# Sheet1.net
KiCad netlist of a schematic drawn in Altium Designer
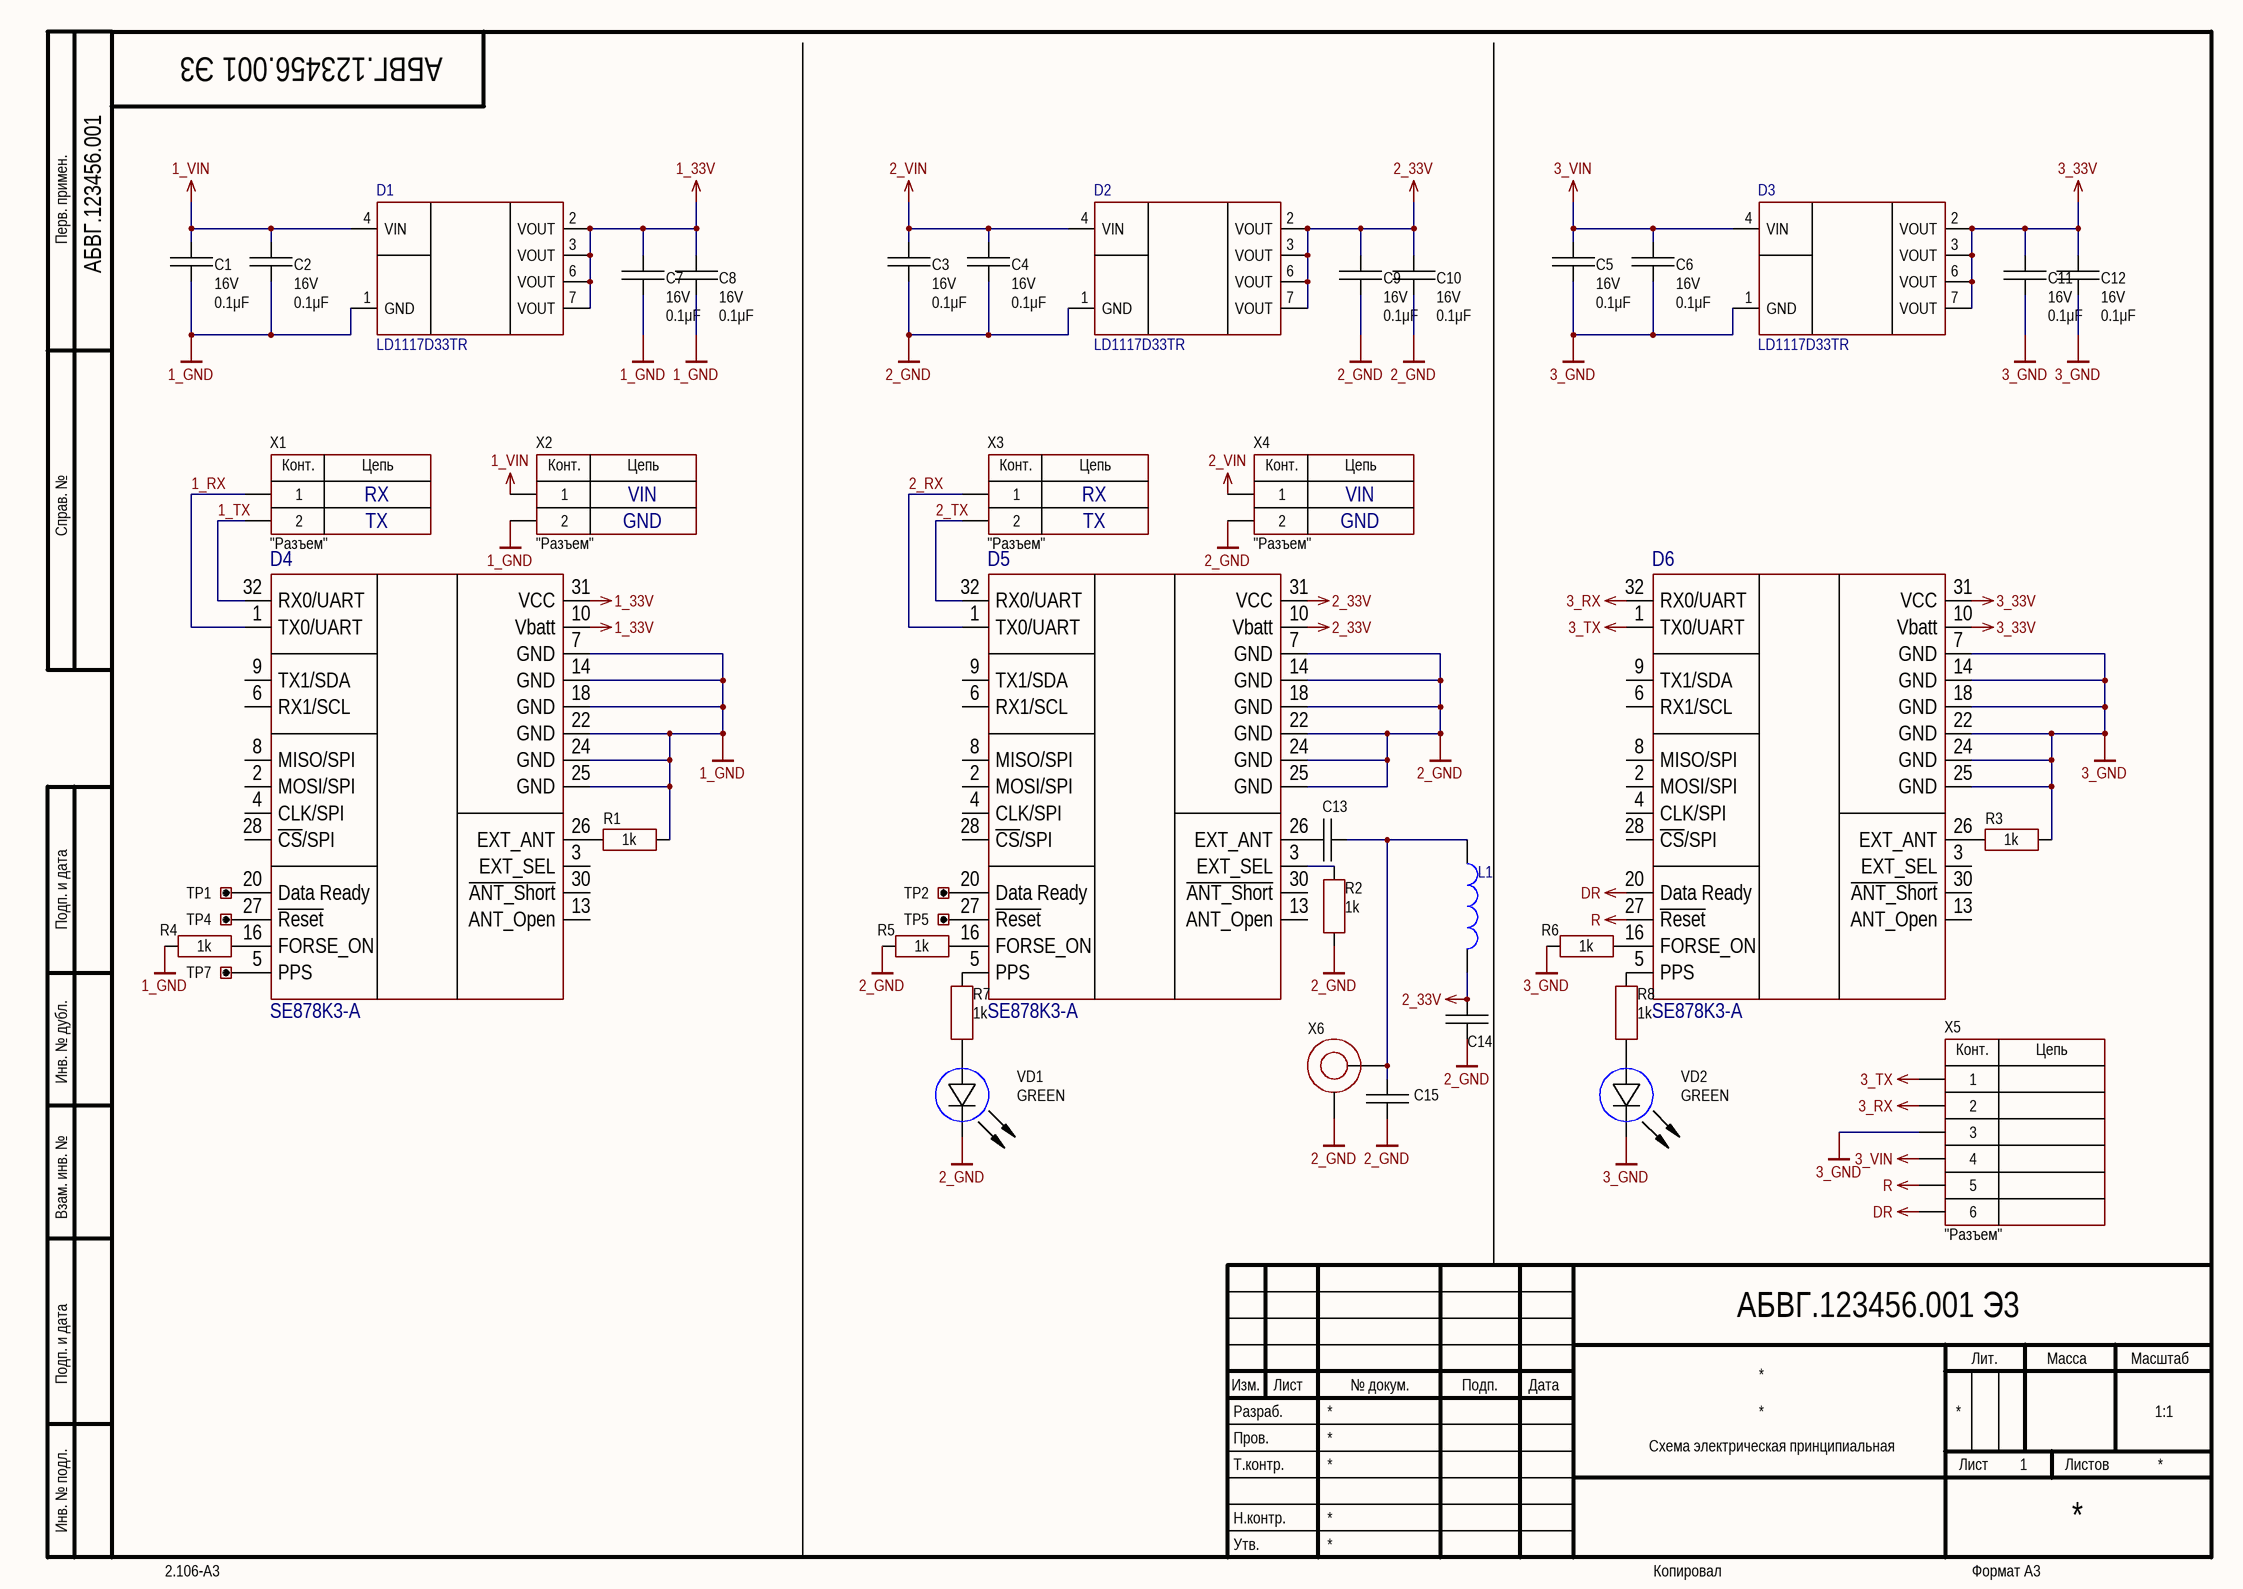
[diagram p0: Sheet1.SchDoc]

(export (version "E")
  (design (tool "Eeschema 10.0.6"))
  (components
    (comp (ref "C1")
      (value "0.1μF")
      (footprint "CAP: 0603")
      (fields
        (field (name "MANUFACTURER") "Yageo")
        (field (name "PARTNUMBER") "CC0603KRX7R7BB104")
        (field (name "VALUEMANUFACTURERPARTNUMBER") "Ceramic capacitor, 0.1μF, X7R, ±10%, 16V, 0603, -55...+125°C")
        (field (name "VOLTAGE") "16V")
      )
      (libsource (lib "Capacitor") (part "Ceramic_0603"))
    )
    (comp (ref "C2")
      (value "0.1μF")
      (footprint "CAP: 0603")
      (fields
        (field (name "MANUFACTURER") "Yageo")
        (field (name "PARTNUMBER") "CC0603KRX7R7BB104")
        (field (name "VALUEMANUFACTURERPARTNUMBER") "Ceramic capacitor, 0.1μF, X7R, ±10%, 16V, 0603, -55...+125°C")
        (field (name "VOLTAGE") "16V")
      )
      (libsource (lib "Capacitor") (part "Ceramic_0603"))
    )
    (comp (ref "C3")
      (value "0.1μF")
      (footprint "CAP: 0603")
      (fields
        (field (name "MANUFACTURER") "Yageo")
        (field (name "PARTNUMBER") "CC0603KRX7R7BB104")
        (field (name "VALUEMANUFACTURERPARTNUMBER") "Ceramic capacitor, 0.1μF, X7R, ±10%, 16V, 0603, -55...+125°C")
        (field (name "VOLTAGE") "16V")
      )
      (libsource (lib "Capacitor") (part "Ceramic_0603"))
    )
    (comp (ref "C4")
      (value "0.1μF")
      (footprint "CAP: 0603")
      (fields
        (field (name "MANUFACTURER") "Yageo")
        (field (name "PARTNUMBER") "CC0603KRX7R7BB104")
        (field (name "VALUEMANUFACTURERPARTNUMBER") "Ceramic capacitor, 0.1μF, X7R, ±10%, 16V, 0603, -55...+125°C")
        (field (name "VOLTAGE") "16V")
      )
      (libsource (lib "Capacitor") (part "Ceramic_0603"))
    )
    (comp (ref "C5")
      (value "0.1μF")
      (footprint "CAP: 0603")
      (fields
        (field (name "MANUFACTURER") "Yageo")
        (field (name "PARTNUMBER") "CC0603KRX7R7BB104")
        (field (name "VALUEMANUFACTURERPARTNUMBER") "Ceramic capacitor, 0.1μF, X7R, ±10%, 16V, 0603, -55...+125°C")
        (field (name "VOLTAGE") "16V")
      )
      (libsource (lib "Capacitor") (part "Ceramic_0603"))
    )
    (comp (ref "C6")
      (value "0.1μF")
      (footprint "CAP: 0603")
      (fields
        (field (name "MANUFACTURER") "Yageo")
        (field (name "PARTNUMBER") "CC0603KRX7R7BB104")
        (field (name "VALUEMANUFACTURERPARTNUMBER") "Ceramic capacitor, 0.1μF, X7R, ±10%, 16V, 0603, -55...+125°C")
        (field (name "VOLTAGE") "16V")
      )
      (libsource (lib "Capacitor") (part "Ceramic_0603"))
    )
    (comp (ref "C7")
      (value "0.1μF")
      (footprint "CAP: 0603")
      (fields
        (field (name "MANUFACTURER") "Yageo")
        (field (name "PARTNUMBER") "CC0603KRX7R7BB104")
        (field (name "VALUEMANUFACTURERPARTNUMBER") "Ceramic capacitor, 0.1μF, X7R, ±10%, 16V, 0603, -55...+125°C")
        (field (name "VOLTAGE") "16V")
      )
      (libsource (lib "Capacitor") (part "Ceramic_0603"))
    )
    (comp (ref "C8")
      (value "0.1μF")
      (footprint "CAP: 0603")
      (fields
        (field (name "MANUFACTURER") "Yageo")
        (field (name "PARTNUMBER") "CC0603KRX7R7BB104")
        (field (name "VALUEMANUFACTURERPARTNUMBER") "Ceramic capacitor, 0.1μF, X7R, ±10%, 16V, 0603, -55...+125°C")
        (field (name "VOLTAGE") "16V")
      )
      (libsource (lib "Capacitor") (part "Ceramic_0603"))
    )
    (comp (ref "C9")
      (value "0.1μF")
      (footprint "CAP: 0603")
      (fields
        (field (name "MANUFACTURER") "Yageo")
        (field (name "PARTNUMBER") "CC0603KRX7R7BB104")
        (field (name "VALUEMANUFACTURERPARTNUMBER") "Ceramic capacitor, 0.1μF, X7R, ±10%, 16V, 0603, -55...+125°C")
        (field (name "VOLTAGE") "16V")
      )
      (libsource (lib "Capacitor") (part "Ceramic_0603"))
    )
    (comp (ref "C10")
      (value "0.1μF")
      (footprint "CAP: 0603")
      (fields
        (field (name "MANUFACTURER") "Yageo")
        (field (name "PARTNUMBER") "CC0603KRX7R7BB104")
        (field (name "VALUEMANUFACTURERPARTNUMBER") "Ceramic capacitor, 0.1μF, X7R, ±10%, 16V, 0603, -55...+125°C")
        (field (name "VOLTAGE") "16V")
      )
      (libsource (lib "Capacitor") (part "Ceramic_0603"))
    )
    (comp (ref "C11")
      (value "0.1μF")
      (footprint "CAP: 0603")
      (fields
        (field (name "MANUFACTURER") "Yageo")
        (field (name "PARTNUMBER") "CC0603KRX7R7BB104")
        (field (name "VALUEMANUFACTURERPARTNUMBER") "Ceramic capacitor, 0.1μF, X7R, ±10%, 16V, 0603, -55...+125°C")
        (field (name "VOLTAGE") "16V")
      )
      (libsource (lib "Capacitor") (part "Ceramic_0603"))
    )
    (comp (ref "C12")
      (value "0.1μF")
      (footprint "CAP: 0603")
      (fields
        (field (name "MANUFACTURER") "Yageo")
        (field (name "PARTNUMBER") "CC0603KRX7R7BB104")
        (field (name "VALUEMANUFACTURERPARTNUMBER") "Ceramic capacitor, 0.1μF, X7R, ±10%, 16V, 0603, -55...+125°C")
        (field (name "VOLTAGE") "16V")
      )
      (libsource (lib "Capacitor") (part "Ceramic_0603"))
    )
    (comp (ref "C13")
      (value "~")
      (footprint "CAP: 0603")
      (fields
        (field (name "MANUFACTURER") "Yageo")
        (field (name "PARTNUMBER") "CC0603KRX7R7BB104")
        (field (name "VALUEMANUFACTURERPARTNUMBER") "Ceramic capacitor, 100Пф, NP0, ±10%, 16V, 0603, -55...+125°C")
      )
      (libsource (lib "Capacitor") (part "Ceramic_0603"))
    )
    (comp (ref "C14")
      (value "~")
      (footprint "CAP: 0603")
      (fields
        (field (name "MANUFACTURER") "Yageo")
        (field (name "PARTNUMBER") "CC0603KRX7R7BB104")
        (field (name "VALUEMANUFACTURERPARTNUMBER") "Ceramic capacitor, 100 пФ, NP0, ±10%, 16V, 0603, -55...+125°C")
      )
      (libsource (lib "Capacitor") (part "Ceramic_0603"))
    )
    (comp (ref "C15")
      (value "~")
      (footprint "CAP: 0603")
      (fields
        (field (name "MANUFACTURER") "Yageo")
        (field (name "PARTNUMBER") "CC0603KRX7R7BB104")
        (field (name "VALUEMANUFACTURERPARTNUMBER") "Ceramic capacitor, 2.2 пФ, NP0, ±10%, 16V, 0603, -55...+125°C")
      )
      (libsource (lib "Capacitor") (part "Ceramic_0603"))
    )
    (comp (ref "D1")
      (value "LD1117D33TR")
      (footprint "8-SOIC")
      (description "Linear voltage regulator")
      (fields (field (name "MANUFACTURER") "ST MICROELECTRONICS"))
      (libsource (lib "IC. Power supply") (part "LD1117D33TR"))
    )
    (comp (ref "D2")
      (value "LD1117D33TR")
      (footprint "8-SOIC")
      (description "Linear voltage regulator")
      (fields (field (name "MANUFACTURER") "ST MICROELECTRONICS"))
      (libsource (lib "IC. Power supply") (part "LD1117D33TR"))
    )
    (comp (ref "D3")
      (value "LD1117D33TR")
      (footprint "8-SOIC")
      (description "Linear voltage regulator")
      (fields (field (name "MANUFACTURER") "ST MICROELECTRONICS"))
      (libsource (lib "IC. Power supply") (part "LD1117D33TR"))
    )
    (comp (ref "D4")
      (value "SE878K3-A")
      (footprint "CustomCase:MOD: SE878K3-A")
      (description "Smart Antenna GNSS Receiver Module")
      (fields
        (field (name "MANUFACTURER") "TELIT")
        (field (name "VALUEMANUFACTURERPARTNUMBER") "SE878K3-A TELIT")
      )
      (libsource (lib "Module") (part "SE878K3-A"))
    )
    (comp (ref "D5")
      (value "SE878K3-A")
      (footprint "CustomCase:MOD: SE878K3-A")
      (description "Smart Antenna GNSS Receiver Module")
      (fields
        (field (name "MANUFACTURER") "TELIT")
        (field (name "VALUEMANUFACTURERPARTNUMBER") "SE878K3-A TELIT")
      )
      (libsource (lib "Module") (part "SE878K3-A"))
    )
    (comp (ref "D6")
      (value "SE878K3-A")
      (footprint "CustomCase:MOD: SE878K3-A")
      (description "Smart Antenna GNSS Receiver Module")
      (fields
        (field (name "MANUFACTURER") "TELIT")
        (field (name "VALUEMANUFACTURERPARTNUMBER") "SE878K3-A TELIT")
      )
      (libsource (lib "Module") (part "SE878K3-A"))
    )
    (comp (ref "L1")
      (value "B09TJL")
      (footprint "IND: BxxT")
      (description "Mini Air Core Inductor")
      (fields (field (name "MANUFACTURER") "COILCRAFT") (field (name "TOLERANCE") "+-5%"))
      (libsource (lib "Inductor") (part "Inductor_air"))
    )
    (comp (ref "R1")
      (value "1k")
      (footprint "RES: 0603")
      (fields
        (field (name "MANUFACTURER") "Yageo")
        (field (name "PARTNUMBER") "RC0603JR-07100RL")
        (field (name "VALUEMANUFACTURERPARTNUMBER") "Resistor film, 1k, ±5%, 0603, 0.1W, -55...+125°C")
      )
      (libsource (lib "Resistor") (part "Resistor_0603"))
    )
    (comp (ref "R2")
      (value "1k")
      (footprint "RES: 0603")
      (fields
        (field (name "MANUFACTURER") "Yageo")
        (field (name "PARTNUMBER") "RC0603JR-07100RL")
        (field (name "VALUEMANUFACTURERPARTNUMBER") "Resistor film, 1k, ±5%, 0603, 0.1W, -55...+125°C")
      )
      (libsource (lib "") (part "Resistor_0603_1"))
    )
    (comp (ref "R3")
      (value "1k")
      (footprint "RES: 0603")
      (fields
        (field (name "MANUFACTURER") "Yageo")
        (field (name "PARTNUMBER") "RC0603JR-07100RL")
        (field (name "VALUEMANUFACTURERPARTNUMBER") "Resistor film, 1k, ±5%, 0603, 0.1W, -55...+125°C")
      )
      (libsource (lib "Resistor") (part "Resistor_0603"))
    )
    (comp (ref "R4")
      (value "1k")
      (footprint "RES: 0603")
      (fields
        (field (name "MANUFACTURER") "Yageo")
        (field (name "PARTNUMBER") "RC0603JR-07100RL")
        (field (name "VALUEMANUFACTURERPARTNUMBER") "Resistor film, 1k, ±5%, 0603, 0.1W, -55...+125°C")
      )
      (libsource (lib "Resistor") (part "Resistor_0603"))
    )
    (comp (ref "R5")
      (value "1k")
      (footprint "RES: 0603")
      (fields
        (field (name "MANUFACTURER") "Yageo")
        (field (name "PARTNUMBER") "RC0603JR-07100RL")
        (field (name "VALUEMANUFACTURERPARTNUMBER") "Resistor film, 1k, ±5%, 0603, 0.1W, -55...+125°C")
      )
      (libsource (lib "Resistor") (part "Resistor_0603"))
    )
    (comp (ref "R6")
      (value "1k")
      (footprint "RES: 0603")
      (fields
        (field (name "MANUFACTURER") "Yageo")
        (field (name "PARTNUMBER") "RC0603JR-07100RL")
        (field (name "VALUEMANUFACTURERPARTNUMBER") "Resistor film, 1k, ±5%, 0603, 0.1W, -55...+125°C")
      )
      (libsource (lib "Resistor") (part "Resistor_0603"))
    )
    (comp (ref "R7")
      (value "1k")
      (footprint "RES: 0603")
      (fields
        (field (name "MANUFACTURER") "Yageo")
        (field (name "PARTNUMBER") "RC0603JR-07100RL")
        (field (name "VALUEMANUFACTURERPARTNUMBER") "Resistor film, 1k, ±5%, 0603, 0.1W, -55...+125°C")
      )
      (libsource (lib "") (part "Resistor_0603_1"))
    )
    (comp (ref "R8")
      (value "1k")
      (footprint "RES: 0603")
      (fields
        (field (name "MANUFACTURER") "Yageo")
        (field (name "PARTNUMBER") "RC0603JR-07100RL")
        (field (name "VALUEMANUFACTURERPARTNUMBER") "Resistor film, 1k, ±5%, 0603, 0.1W, -55...+125°C")
      )
      (libsource (lib "") (part "Resistor_0603_1"))
    )
    (comp (ref "TP1")
      (value "~")
      (footprint "CustomCase:CON: 5000 (Keystone)")
      (fields
        (field (name "MANUFACTURER") "Keystone")
        (field (name "VALUEMANUFACTURERPARTNUMBER") "Test point, Keystone, 5001")
        (field (name "PARTNUMBER") "5001")
      )
      (libsource (lib "Connector") (part "Connector_Test_Point"))
    )
    (comp (ref "TP2")
      (value "~")
      (footprint "CustomCase:CON: 5000 (Keystone)")
      (fields
        (field (name "MANUFACTURER") "Keystone")
        (field (name "VALUEMANUFACTURERPARTNUMBER") "Test point, Keystone, 5001")
        (field (name "PARTNUMBER") "5001")
      )
      (libsource (lib "Connector") (part "Connector_Test_Point"))
    )
    (comp (ref "TP4")
      (value "~")
      (footprint "CustomCase:CON: 5000 (Keystone)")
      (fields
        (field (name "MANUFACTURER") "Keystone")
        (field (name "VALUEMANUFACTURERPARTNUMBER") "Test point, Keystone, 5001")
        (field (name "PARTNUMBER") "5001")
      )
      (libsource (lib "Connector") (part "Connector_Test_Point"))
    )
    (comp (ref "TP5")
      (value "~")
      (footprint "CustomCase:CON: 5000 (Keystone)")
      (fields
        (field (name "MANUFACTURER") "Keystone")
        (field (name "VALUEMANUFACTURERPARTNUMBER") "Test point, Keystone, 5001")
        (field (name "PARTNUMBER") "5001")
      )
      (libsource (lib "Connector") (part "Connector_Test_Point"))
    )
    (comp (ref "TP7")
      (value "~")
      (footprint "CustomCase:CON: 5000 (Keystone)")
      (fields
        (field (name "MANUFACTURER") "Keystone")
        (field (name "VALUEMANUFACTURERPARTNUMBER") "Test point, Keystone, 5001")
        (field (name "PARTNUMBER") "5001")
      )
      (libsource (lib "Connector") (part "Connector_Test_Point"))
    )
    (comp (ref "VD1")
      (value "~")
      (footprint "LED: 0603G")
      (fields
        (field (name "VALUEMANUFACTURERPARTNUMBER") "LED, Green, *, *, *, -55...+150°C")
        (field (name "COLOR") "GREEN")
      )
      (libsource (lib "Diode") (part "LED_single"))
    )
    (comp (ref "VD2")
      (value "~")
      (footprint "LED: 0603G")
      (fields
        (field (name "VALUEMANUFACTURERPARTNUMBER") "LED, Green, *, *, *, -55...+150°C")
        (field (name "COLOR") "GREEN")
      )
      (libsource (lib "Diode") (part "LED_single"))
    )
    (comp (ref "X1")
      (value "~")
      (footprint "CustomCase:CON: PLS-2")
      (fields
        (field (name "MANUFACTURER") "Connfly")
        (field (name "VALUEMANUFACTURERPARTNUMBER") "Connector, 2pin, 2.54mm, 500VAC, 3A")
        (field (name "PARTNUMBER") "PLS-2")
        (field (name "COMMENTTEXT") "\"Разъем\"")
      )
      (libsource (lib "Connector") (part "PLS-2"))
    )
    (comp (ref "X2")
      (value "~")
      (footprint "CustomCase:CON: PLS-2")
      (fields
        (field (name "MANUFACTURER") "Connfly")
        (field (name "VALUEMANUFACTURERPARTNUMBER") "Connector, 2pin, 2.54mm, 500VAC, 3A")
        (field (name "PARTNUMBER") "PLS-2")
        (field (name "COMMENTTEXT") "\"Разъем\"")
      )
      (libsource (lib "Connector") (part "PLS-2"))
    )
    (comp (ref "X3")
      (value "~")
      (footprint "CustomCase:CON: PLS-2")
      (fields
        (field (name "MANUFACTURER") "Connfly")
        (field (name "VALUEMANUFACTURERPARTNUMBER") "Connector, 2pin, 2.54mm, 500VAC, 3A")
        (field (name "PARTNUMBER") "PLS-2")
        (field (name "COMMENTTEXT") "\"Разъем\"")
      )
      (libsource (lib "Connector") (part "PLS-2"))
    )
    (comp (ref "X4")
      (value "~")
      (footprint "CustomCase:CON: PLS-2")
      (fields
        (field (name "MANUFACTURER") "Connfly")
        (field (name "VALUEMANUFACTURERPARTNUMBER") "Connector, 2pin, 2.54mm, 500VAC, 3A")
        (field (name "PARTNUMBER") "PLS-2")
        (field (name "COMMENTTEXT") "\"Разъем\"")
      )
      (libsource (lib "Connector") (part "PLS-2"))
    )
    (comp (ref "X5")
      (value "~")
      (footprint "CustomCase:CON: PLS-6")
      (fields
        (field (name "MANUFACTURER") "Connfly")
        (field (name "VALUEMANUFACTURERPARTNUMBER") "Connector, 6pin, 2.54mm, 500VAC, 3A")
        (field (name "PARTNUMBER") "PLS-6")
        (field (name "COMMENTTEXT") "\"Разъем\"")
      )
      (libsource (lib "Connector") (part "PLS-6"))
    )
    (comp (ref "X6")
      (value "~")
      (footprint "CustomCase:CON: u.Fl")
      (fields
        (field (name "MANUFACTURER") "Hirose Electric")
        (field (name "VALUEMANUFACTURERPARTNUMBER") "Connector u.FL, 50 Ohm, 6GHz")
        (field (name "PARTNUMBER") "U.FL-R-SMT(01)")
      )
      (libsource (lib "Connector") (part "Connector_uFL"))
    )
  )
  (nets
    (net (code "1") (name "/1_RX") (class "Default")
      (node (ref "D4") (pin "1") (pinfunction "TX0/UART_1") (pintype "passive"))
      (node (ref "X1") (pin "1") (pinfunction "1_1") (pintype "passive"))
    )
    (net (code "2") (name "/1_TX") (class "Default")
      (node (ref "D4") (pin "32") (pinfunction "RX0/UART_32") (pintype "passive"))
      (node (ref "X1") (pin "2") (pinfunction "2_2") (pintype "passive"))
    )
    (net (code "3") (name "/2_RX") (class "Default")
      (node (ref "D5") (pin "1") (pinfunction "TX0/UART_1") (pintype "passive"))
      (node (ref "X3") (pin "1") (pinfunction "1_1") (pintype "passive"))
    )
    (net (code "4") (name "/2_TX") (class "Default")
      (node (ref "D5") (pin "32") (pinfunction "RX0/UART_32") (pintype "passive"))
      (node (ref "X3") (pin "2") (pinfunction "2_2") (pintype "passive"))
    )
    (net (code "5") (name "1_33V") (class "Default")
      (node (ref "C7") (pin "2") (pinfunction "2_2") (pintype "power_in"))
      (node (ref "C8") (pin "2") (pinfunction "2_2") (pintype "power_in"))
      (node (ref "D1") (pin "2") (pinfunction "VOUT_2") (pintype "power_in"))
      (node (ref "D1") (pin "3") (pinfunction "VOUT_3") (pintype "power_in"))
      (node (ref "D1") (pin "6") (pinfunction "VOUT_6") (pintype "power_in"))
      (node (ref "D1") (pin "7") (pinfunction "VOUT_7") (pintype "power_in"))
      (node (ref "D4") (pin "10") (pinfunction "Vbatt_10") (pintype "passive"))
      (node (ref "D4") (pin "31") (pinfunction "VCC_31") (pintype "passive"))
    )
    (net (code "6") (name "1_GND") (class "Default")
      (node (ref "C1") (pin "1") (pinfunction "1_1") (pintype "power_in"))
      (node (ref "C2") (pin "1") (pinfunction "1_1") (pintype "power_in"))
      (node (ref "C7") (pin "1") (pinfunction "1_1") (pintype "power_in"))
      (node (ref "C8") (pin "1") (pinfunction "1_1") (pintype "power_in"))
      (node (ref "D1") (pin "1") (pinfunction "GND_1") (pintype "power_in"))
      (node (ref "D4") (pin "14") (pinfunction "GND_14") (pintype "passive"))
      (node (ref "D4") (pin "18") (pinfunction "GND_18") (pintype "passive"))
      (node (ref "D4") (pin "22") (pinfunction "GND_22") (pintype "passive"))
      (node (ref "D4") (pin "24") (pinfunction "GND_24") (pintype "passive"))
      (node (ref "D4") (pin "25") (pinfunction "GND_25") (pintype "passive"))
      (node (ref "D4") (pin "7") (pinfunction "GND_7") (pintype "passive"))
      (node (ref "R1") (pin "2") (pinfunction "2_2") (pintype "passive"))
      (node (ref "R4") (pin "1") (pinfunction "1_1") (pintype "passive"))
      (node (ref "X2") (pin "2") (pinfunction "2_2") (pintype "passive"))
    )
    (net (code "7") (name "1_VIN") (class "Default")
      (node (ref "C1") (pin "2") (pinfunction "2_2") (pintype "power_in"))
      (node (ref "C2") (pin "2") (pinfunction "2_2") (pintype "power_in"))
      (node (ref "D1") (pin "4") (pinfunction "VIN_4") (pintype "power_in"))
      (node (ref "X2") (pin "1") (pinfunction "1_1") (pintype "passive"))
    )
    (net (code "8") (name "2_33V") (class "Default")
      (node (ref "C10") (pin "2") (pinfunction "2_2") (pintype "power_in"))
      (node (ref "C14") (pin "2") (pinfunction "2_2") (pintype "power_in"))
      (node (ref "C9") (pin "2") (pinfunction "2_2") (pintype "power_in"))
      (node (ref "D2") (pin "2") (pinfunction "VOUT_2") (pintype "power_in"))
      (node (ref "D2") (pin "3") (pinfunction "VOUT_3") (pintype "power_in"))
      (node (ref "D2") (pin "6") (pinfunction "VOUT_6") (pintype "power_in"))
      (node (ref "D2") (pin "7") (pinfunction "VOUT_7") (pintype "power_in"))
      (node (ref "D5") (pin "10") (pinfunction "Vbatt_10") (pintype "passive"))
      (node (ref "D5") (pin "31") (pinfunction "VCC_31") (pintype "passive"))
      (node (ref "L1") (pin "1") (pinfunction "1_1") (pintype "passive"))
    )
    (net (code "9") (name "2_GND") (class "Default")
      (node (ref "C10") (pin "1") (pinfunction "1_1") (pintype "power_in"))
      (node (ref "C14") (pin "1") (pinfunction "1_1") (pintype "power_in"))
      (node (ref "C15") (pin "1") (pinfunction "1_1") (pintype "power_in"))
      (node (ref "C3") (pin "1") (pinfunction "1_1") (pintype "power_in"))
      (node (ref "C4") (pin "1") (pinfunction "1_1") (pintype "power_in"))
      (node (ref "C9") (pin "1") (pinfunction "1_1") (pintype "power_in"))
      (node (ref "D2") (pin "1") (pinfunction "GND_1") (pintype "power_in"))
      (node (ref "D5") (pin "14") (pinfunction "GND_14") (pintype "passive"))
      (node (ref "D5") (pin "18") (pinfunction "GND_18") (pintype "passive"))
      (node (ref "D5") (pin "22") (pinfunction "GND_22") (pintype "passive"))
      (node (ref "D5") (pin "24") (pinfunction "GND_24") (pintype "passive"))
      (node (ref "D5") (pin "25") (pinfunction "GND_25") (pintype "passive"))
      (node (ref "D5") (pin "7") (pinfunction "GND_7") (pintype "passive"))
      (node (ref "R2") (pin "1") (pinfunction "1_1") (pintype "passive"))
      (node (ref "R5") (pin "1") (pinfunction "1_1") (pintype "passive"))
      (node (ref "VD1") (pin "2") (pinfunction "C_2") (pintype "passive"))
      (node (ref "X4") (pin "2") (pinfunction "2_2") (pintype "passive"))
      (node (ref "X6") (pin "2") (pinfunction "2_2") (pintype "passive"))
    )
    (net (code "10") (name "2_VIN") (class "Default")
      (node (ref "C3") (pin "2") (pinfunction "2_2") (pintype "power_in"))
      (node (ref "C4") (pin "2") (pinfunction "2_2") (pintype "power_in"))
      (node (ref "D2") (pin "4") (pinfunction "VIN_4") (pintype "power_in"))
      (node (ref "X4") (pin "1") (pinfunction "1_1") (pintype "passive"))
    )
    (net (code "11") (name "3_33V") (class "Default")
      (node (ref "C11") (pin "2") (pinfunction "2_2") (pintype "power_in"))
      (node (ref "C12") (pin "2") (pinfunction "2_2") (pintype "power_in"))
      (node (ref "D3") (pin "2") (pinfunction "VOUT_2") (pintype "power_in"))
      (node (ref "D3") (pin "3") (pinfunction "VOUT_3") (pintype "power_in"))
      (node (ref "D3") (pin "6") (pinfunction "VOUT_6") (pintype "power_in"))
      (node (ref "D3") (pin "7") (pinfunction "VOUT_7") (pintype "power_in"))
      (node (ref "D6") (pin "10") (pinfunction "Vbatt_10") (pintype "passive"))
      (node (ref "D6") (pin "31") (pinfunction "VCC_31") (pintype "passive"))
    )
    (net (code "12") (name "3_GND") (class "Default")
      (node (ref "C11") (pin "1") (pinfunction "1_1") (pintype "power_in"))
      (node (ref "C12") (pin "1") (pinfunction "1_1") (pintype "power_in"))
      (node (ref "C5") (pin "1") (pinfunction "1_1") (pintype "power_in"))
      (node (ref "C6") (pin "1") (pinfunction "1_1") (pintype "power_in"))
      (node (ref "D3") (pin "1") (pinfunction "GND_1") (pintype "power_in"))
      (node (ref "D6") (pin "14") (pinfunction "GND_14") (pintype "passive"))
      (node (ref "D6") (pin "18") (pinfunction "GND_18") (pintype "passive"))
      (node (ref "D6") (pin "22") (pinfunction "GND_22") (pintype "passive"))
      (node (ref "D6") (pin "24") (pinfunction "GND_24") (pintype "passive"))
      (node (ref "D6") (pin "25") (pinfunction "GND_25") (pintype "passive"))
      (node (ref "D6") (pin "7") (pinfunction "GND_7") (pintype "passive"))
      (node (ref "R3") (pin "2") (pinfunction "2_2") (pintype "passive"))
      (node (ref "R6") (pin "1") (pinfunction "1_1") (pintype "passive"))
      (node (ref "VD2") (pin "2") (pinfunction "C_2") (pintype "passive"))
      (node (ref "X5") (pin "3") (pinfunction "3_3") (pintype "power_in"))
    )
    (net (code "13") (name "3_RX") (class "Default")
      (node (ref "D6") (pin "32") (pinfunction "RX0/UART_32") (pintype "passive"))
      (node (ref "X5") (pin "2") (pinfunction "2_2") (pintype "passive"))
    )
    (net (code "14") (name "3_TX") (class "Default")
      (node (ref "D6") (pin "1") (pinfunction "TX0/UART_1") (pintype "passive"))
      (node (ref "X5") (pin "1") (pinfunction "1_1") (pintype "passive"))
    )
    (net (code "15") (name "3_VIN") (class "Default")
      (node (ref "C5") (pin "2") (pinfunction "2_2") (pintype "power_in"))
      (node (ref "C6") (pin "2") (pinfunction "2_2") (pintype "power_in"))
      (node (ref "D3") (pin "4") (pinfunction "VIN_4") (pintype "power_in"))
      (node (ref "X5") (pin "4") (pinfunction "4_4") (pintype "power_in"))
    )
    (net (code "16") (name "DR") (class "Default")
      (node (ref "D6") (pin "20") (pinfunction "Data_Ready_20") (pintype "passive"))
      (node (ref "X5") (pin "6") (pinfunction "6_6") (pintype "power_in"))
    )
    (net (code "17") (name "Net-(C13-Pad1)") (class "Default")
      (node (ref "C13") (pin "1") (pinfunction "1_1") (pintype "power_in"))
      (node (ref "C15") (pin "2") (pinfunction "2_2") (pintype "power_in"))
      (node (ref "L1") (pin "2") (pinfunction "2_2") (pintype "passive"))
      (node (ref "X6") (pin "1") (pinfunction "1_1") (pintype "passive"))
    )
    (net (code "18") (name "Net-(D4-Data_Ready)") (class "Default")
      (node (ref "D4") (pin "20") (pinfunction "Data_Ready_20") (pintype "passive"))
      (node (ref "TP1") (pin "1") (pinfunction "1_1") (pintype "passive"))
    )
    (net (code "19") (name "Net-(D4-EXT_ANT)") (class "Default")
      (node (ref "D4") (pin "26") (pinfunction "EXT_ANT_26") (pintype "passive"))
      (node (ref "R1") (pin "1") (pinfunction "1_1") (pintype "passive"))
    )
    (net (code "20") (name "Net-(D4-FORSE_ON)") (class "Default")
      (node (ref "D4") (pin "16") (pinfunction "FORSE_ON_16") (pintype "passive"))
      (node (ref "R4") (pin "2") (pinfunction "2_2") (pintype "passive"))
    )
    (net (code "21") (name "Net-(D4-PPS)") (class "Default")
      (node (ref "D4") (pin "5") (pinfunction "PPS_5") (pintype "passive"))
      (node (ref "TP7") (pin "1") (pinfunction "1_1") (pintype "passive"))
    )
    (net (code "22") (name "Net-(D4-~{Reset})") (class "Default")
      (node (ref "D4") (pin "27") (pinfunction "~{Reset}_27") (pintype "passive"))
      (node (ref "TP4") (pin "1") (pinfunction "1_1") (pintype "passive"))
    )
    (net (code "23") (name "Net-(D5-Data_Ready)") (class "Default")
      (node (ref "D5") (pin "20") (pinfunction "Data_Ready_20") (pintype "passive"))
      (node (ref "TP2") (pin "1") (pinfunction "1_1") (pintype "passive"))
    )
    (net (code "24") (name "Net-(D5-EXT_ANT)") (class "Default")
      (node (ref "C13") (pin "2") (pinfunction "2_2") (pintype "power_in"))
      (node (ref "D5") (pin "26") (pinfunction "EXT_ANT_26") (pintype "passive"))
    )
    (net (code "25") (name "Net-(D5-EXT_SEL)") (class "Default")
      (node (ref "D5") (pin "3") (pinfunction "EXT_SEL_3") (pintype "passive"))
      (node (ref "R2") (pin "2") (pinfunction "2_2") (pintype "passive"))
    )
    (net (code "26") (name "Net-(D5-FORSE_ON)") (class "Default")
      (node (ref "D5") (pin "16") (pinfunction "FORSE_ON_16") (pintype "passive"))
      (node (ref "R5") (pin "2") (pinfunction "2_2") (pintype "passive"))
    )
    (net (code "27") (name "Net-(D5-PPS)") (class "Default")
      (node (ref "D5") (pin "5") (pinfunction "PPS_5") (pintype "passive"))
      (node (ref "R7") (pin "2") (pinfunction "2_2") (pintype "passive"))
    )
    (net (code "28") (name "Net-(D5-~{Reset})") (class "Default")
      (node (ref "D5") (pin "27") (pinfunction "~{Reset}_27") (pintype "passive"))
      (node (ref "TP5") (pin "1") (pinfunction "1_1") (pintype "passive"))
    )
    (net (code "29") (name "Net-(D6-EXT_ANT)") (class "Default")
      (node (ref "D6") (pin "26") (pinfunction "EXT_ANT_26") (pintype "passive"))
      (node (ref "R3") (pin "1") (pinfunction "1_1") (pintype "passive"))
    )
    (net (code "30") (name "Net-(D6-FORSE_ON)") (class "Default")
      (node (ref "D6") (pin "16") (pinfunction "FORSE_ON_16") (pintype "passive"))
      (node (ref "R6") (pin "2") (pinfunction "2_2") (pintype "passive"))
    )
    (net (code "31") (name "Net-(D6-PPS)") (class "Default")
      (node (ref "D6") (pin "5") (pinfunction "PPS_5") (pintype "passive"))
      (node (ref "R8") (pin "2") (pinfunction "2_2") (pintype "passive"))
    )
    (net (code "32") (name "Net-(VD1-A)") (class "Default")
      (node (ref "R7") (pin "1") (pinfunction "1_1") (pintype "passive"))
      (node (ref "VD1") (pin "1") (pinfunction "A_1") (pintype "passive"))
    )
    (net (code "33") (name "Net-(VD2-A)") (class "Default")
      (node (ref "R8") (pin "1") (pinfunction "1_1") (pintype "passive"))
      (node (ref "VD2") (pin "1") (pinfunction "A_1") (pintype "passive"))
    )
    (net (code "34") (name "R") (class "Default")
      (node (ref "D6") (pin "27") (pinfunction "~{Reset}_27") (pintype "passive"))
      (node (ref "X5") (pin "5") (pinfunction "5_5") (pintype "power_in"))
    )
    (net (code "35") (name "unconnected-(D4-ANT_Open-Pad13)") (class "Default")
      (node (ref "D4") (pin "13") (pinfunction "ANT_Open_13") (pintype "passive"))
    )
    (net (code "36") (name "unconnected-(D4-CLK{slash}SPI-Pad4)") (class "Default")
      (node (ref "D4") (pin "4") (pinfunction "CLK/SPI_4") (pintype "passive"))
    )
    (net (code "37") (name "unconnected-(D4-EXT_SEL-Pad3)") (class "Default")
      (node (ref "D4") (pin "3") (pinfunction "EXT_SEL_3") (pintype "passive"))
    )
    (net (code "38") (name "unconnected-(D4-MISO{slash}SPI-Pad8)") (class "Default")
      (node (ref "D4") (pin "8") (pinfunction "MISO/SPI_8") (pintype "passive"))
    )
    (net (code "39") (name "unconnected-(D4-MOSI{slash}SPI-Pad2)") (class "Default")
      (node (ref "D4") (pin "2") (pinfunction "MOSI/SPI_2") (pintype "passive"))
    )
    (net (code "40") (name "unconnected-(D4-RX1{slash}SCL-Pad6)") (class "Default")
      (node (ref "D4") (pin "6") (pinfunction "RX1/SCL_6") (pintype "passive"))
    )
    (net (code "41") (name "unconnected-(D4-TX1{slash}SDA-Pad9)") (class "Default")
      (node (ref "D4") (pin "9") (pinfunction "TX1/SDA_9") (pintype "passive"))
    )
    (net (code "42") (name "unconnected-(D4-~{ANT_Short}-Pad30)") (class "Default")
      (node (ref "D4") (pin "30") (pinfunction "~{ANT_Short}_30") (pintype "passive"))
    )
    (net (code "43") (name "unconnected-(D4-~{CS}{slash}SPI-Pad28)") (class "Default")
      (node (ref "D4") (pin "28") (pinfunction "~{CS}/SPI_28") (pintype "passive"))
    )
    (net (code "44") (name "unconnected-(D5-ANT_Open-Pad13)") (class "Default")
      (node (ref "D5") (pin "13") (pinfunction "ANT_Open_13") (pintype "passive"))
    )
    (net (code "45") (name "unconnected-(D5-CLK{slash}SPI-Pad4)") (class "Default")
      (node (ref "D5") (pin "4") (pinfunction "CLK/SPI_4") (pintype "passive"))
    )
    (net (code "46") (name "unconnected-(D5-MISO{slash}SPI-Pad8)") (class "Default")
      (node (ref "D5") (pin "8") (pinfunction "MISO/SPI_8") (pintype "passive"))
    )
    (net (code "47") (name "unconnected-(D5-MOSI{slash}SPI-Pad2)") (class "Default")
      (node (ref "D5") (pin "2") (pinfunction "MOSI/SPI_2") (pintype "passive"))
    )
    (net (code "48") (name "unconnected-(D5-RX1{slash}SCL-Pad6)") (class "Default")
      (node (ref "D5") (pin "6") (pinfunction "RX1/SCL_6") (pintype "passive"))
    )
    (net (code "49") (name "unconnected-(D5-TX1{slash}SDA-Pad9)") (class "Default")
      (node (ref "D5") (pin "9") (pinfunction "TX1/SDA_9") (pintype "passive"))
    )
    (net (code "50") (name "unconnected-(D5-~{ANT_Short}-Pad30)") (class "Default")
      (node (ref "D5") (pin "30") (pinfunction "~{ANT_Short}_30") (pintype "passive"))
    )
    (net (code "51") (name "unconnected-(D5-~{CS}{slash}SPI-Pad28)") (class "Default")
      (node (ref "D5") (pin "28") (pinfunction "~{CS}/SPI_28") (pintype "passive"))
    )
    (net (code "52") (name "unconnected-(D6-ANT_Open-Pad13)") (class "Default")
      (node (ref "D6") (pin "13") (pinfunction "ANT_Open_13") (pintype "passive"))
    )
    (net (code "53") (name "unconnected-(D6-CLK{slash}SPI-Pad4)") (class "Default")
      (node (ref "D6") (pin "4") (pinfunction "CLK/SPI_4") (pintype "passive"))
    )
    (net (code "54") (name "unconnected-(D6-EXT_SEL-Pad3)") (class "Default")
      (node (ref "D6") (pin "3") (pinfunction "EXT_SEL_3") (pintype "passive"))
    )
    (net (code "55") (name "unconnected-(D6-MISO{slash}SPI-Pad8)") (class "Default")
      (node (ref "D6") (pin "8") (pinfunction "MISO/SPI_8") (pintype "passive"))
    )
    (net (code "56") (name "unconnected-(D6-MOSI{slash}SPI-Pad2)") (class "Default")
      (node (ref "D6") (pin "2") (pinfunction "MOSI/SPI_2") (pintype "passive"))
    )
    (net (code "57") (name "unconnected-(D6-RX1{slash}SCL-Pad6)") (class "Default")
      (node (ref "D6") (pin "6") (pinfunction "RX1/SCL_6") (pintype "passive"))
    )
    (net (code "58") (name "unconnected-(D6-TX1{slash}SDA-Pad9)") (class "Default")
      (node (ref "D6") (pin "9") (pinfunction "TX1/SDA_9") (pintype "passive"))
    )
    (net (code "59") (name "unconnected-(D6-~{ANT_Short}-Pad30)") (class "Default")
      (node (ref "D6") (pin "30") (pinfunction "~{ANT_Short}_30") (pintype "passive"))
    )
    (net (code "60") (name "unconnected-(D6-~{CS}{slash}SPI-Pad28)") (class "Default")
      (node (ref "D6") (pin "28") (pinfunction "~{CS}/SPI_28") (pintype "passive"))
    )
  )
)
